# medusa-ai-power.net
KiCad netlist of a schematic drawn in Altium Designer
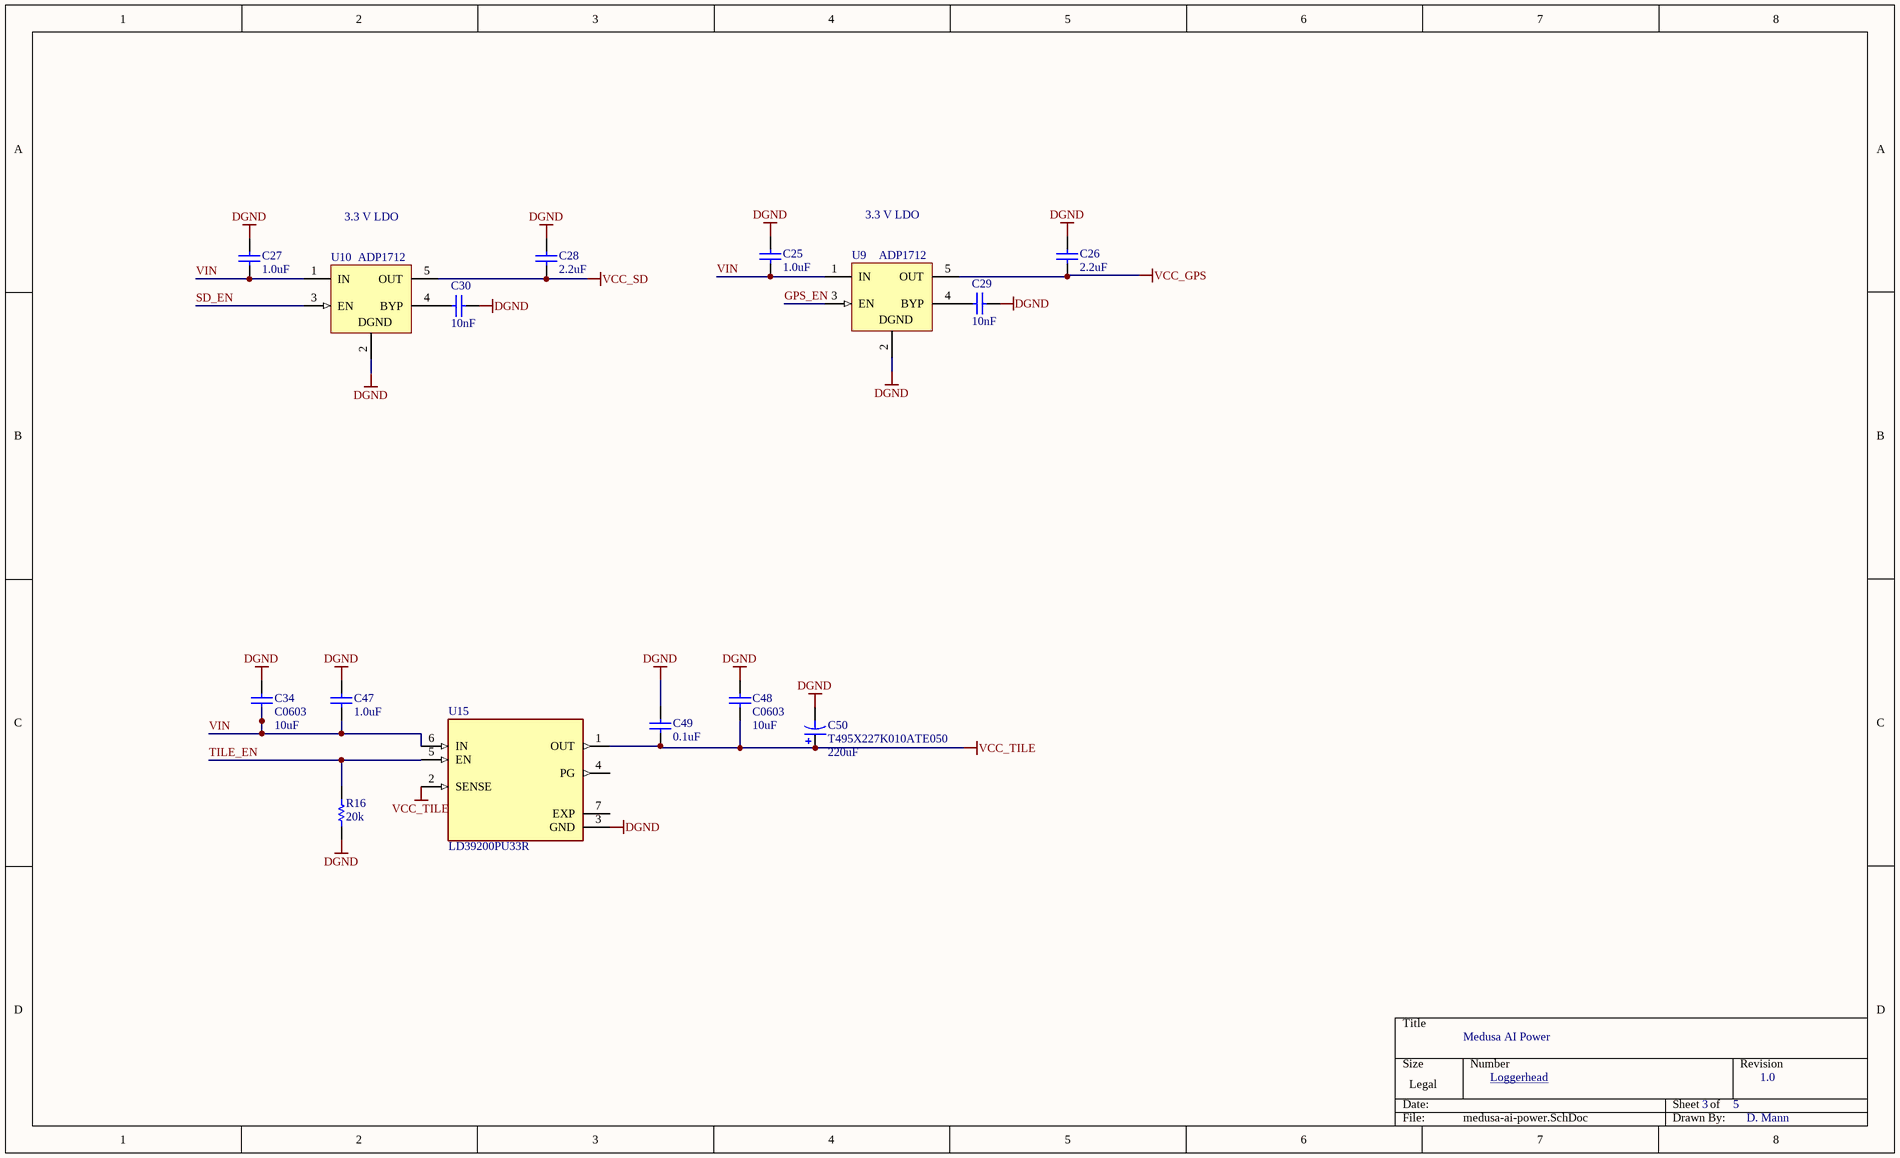
[diagram p0: medusa-ai-power.SchDoc]

(export (version "E")
  (design (tool "Eeschema 10.0.6"))
  (components
    (comp (ref "C25")
      (value "1.0uF")
      (footprint "0402")
      (description "Ceramic Chip Capacitor - Standard")
      (fields (field (name "PUBLISHER") "Altium Limited"))
      (libsource (lib "KEMET Chip Capacitor") (part "C0402"))
    )
    (comp (ref "C26")
      (value "2.2uF")
      (footprint "0402")
      (description "Ceramic Chip Capacitor - Standard")
      (fields (field (name "PUBLISHER") "Altium Limited"))
      (libsource (lib "KEMET Chip Capacitor") (part "C0402"))
    )
    (comp (ref "C27")
      (value "1.0uF")
      (footprint "0402")
      (description "Ceramic Chip Capacitor - Standard")
      (fields (field (name "PUBLISHER") "Altium Limited"))
      (libsource (lib "KEMET Chip Capacitor") (part "C0402"))
    )
    (comp (ref "C28")
      (value "2.2uF")
      (footprint "0402")
      (description "Ceramic Chip Capacitor - Standard")
      (fields (field (name "PUBLISHER") "Altium Limited"))
      (libsource (lib "KEMET Chip Capacitor") (part "C0402"))
    )
    (comp (ref "C29")
      (value "10nF")
      (footprint "0402")
      (description "Ceramic Chip Capacitor - Standard")
      (fields (field (name "PUBLISHER") "Altium Limited"))
      (libsource (lib "KEMET Chip Capacitor") (part "C0402"))
    )
    (comp (ref "C30")
      (value "10nF")
      (footprint "0402")
      (description "Ceramic Chip Capacitor - Standard")
      (fields (field (name "PUBLISHER") "Altium Limited"))
      (libsource (lib "KEMET Chip Capacitor") (part "C0402"))
    )
    (comp (ref "C34")
      (value "C0603")
      (footprint "0603")
      (description "Ceramic Chip Capacitor - Standard")
      (fields (field (name "ALTIUM_VALUE") "10uF") (field (name "PUBLISHER") "Altium Limited"))
      (libsource (lib "KEMET Chip Capacitor") (part "C0603"))
    )
    (comp (ref "C47")
      (value "1.0uF")
      (footprint "0402")
      (description "Ceramic Chip Capacitor - Standard")
      (fields (field (name "PUBLISHER") "Altium Limited"))
      (libsource (lib "KEMET Chip Capacitor") (part "C0402"))
    )
    (comp (ref "C48")
      (value "C0603")
      (footprint "0603")
      (description "Ceramic Chip Capacitor - Standard")
      (fields (field (name "ALTIUM_VALUE") "10uF") (field (name "PUBLISHER") "Altium Limited"))
      (libsource (lib "KEMET Chip Capacitor") (part "C0603"))
    )
    (comp (ref "C49")
      (value "0.1uF")
      (footprint "0402")
      (description "Ceramic Chip Capacitor - Standard")
      (fields (field (name "PUBLISHER") "Altium Limited"))
      (libsource (lib "KEMET Chip Capacitor") (part "C0402"))
    )
    (comp (ref "C50")
      (value "T495X227K010ATE050")
      (footprint "X")
      (description "Solid Tantalum Chip Capacitor, Standard T495 Series - Low ESR, Surge Robust")
      (fields (field (name "ALTIUM_VALUE") "220uF") (field (name "PUBLISHER") "Altium Limited"))
      (libsource (lib "KEMET Chip Capacitor") (part "T495X"))
    )
    (comp (ref "R16")
      (value "20k")
      (footprint "3-0603")
      (fields (field (name "PUBLISHER") "Altium Limited"))
      (libsource (lib "Panasonic Resistor") (part "ERJ3RK"))
    )
    (comp (ref "U9")
      (value "ADP1712")
      (footprint "MF05A_N")
      (description "Micropower, 150mA Low-Noise Ultra Low-Dropout CMOS Voltage Regulator")
      (fields
        (field (name "PARTNUMBER") "LP3985IM5-3.3")
        (field (name "MANUFACTURER") "National Semiconductor")
        (field (name "PUBLISHER") "Altium Limited")
      )
      (libsource (lib "NSC LDO") (part "LP3985IM5-3.3"))
    )
    (comp (ref "U10")
      (value "ADP1712")
      (footprint "MF05A_N")
      (description "Micropower, 150mA Low-Noise Ultra Low-Dropout CMOS Voltage Regulator")
      (fields
        (field (name "PARTNUMBER") "LP3985IM5-3.3")
        (field (name "MANUFACTURER") "National Semiconductor")
        (field (name "PUBLISHER") "Altium Limited")
      )
      (libsource (lib "NSC LDO") (part "LP3985IM5-3.3"))
    )
    (comp (ref "U15")
      (value "LD39200PU33R")
      (footprint "SON95P300X300X100-7N")
      (description "Linear Voltage Regulator IC 1 Output 2A 6-DFN _3x3_")
      (fields (field (name "MF") "STMicroelectronics"))
      (libsource (lib "LD39200PU33R") (part "LD39200PU33R"))
    )
  )
  (nets
    (net (code "1") (name "/GPS_EN") (class "Default")
      (node (ref "U9") (pin "3") (pinfunction "EN_3") (pintype "input"))
    )
    (net (code "2") (name "/SD_EN") (class "Default")
      (node (ref "U10") (pin "3") (pinfunction "EN_3") (pintype "input"))
    )
    (net (code "3") (name "/TILE_EN") (class "Default")
      (node (ref "R16") (pin "1") (pinfunction "1_1") (pintype "passive"))
      (node (ref "U15") (pin "5") (pinfunction "EN_5") (pintype "input"))
    )
    (net (code "4") (name "/VIN") (class "Default")
      (node (ref "C25") (pin "1") (pinfunction "1_1") (pintype "passive"))
      (node (ref "C27") (pin "1") (pinfunction "1_1") (pintype "passive"))
      (node (ref "C34") (pin "2") (pinfunction "2_2") (pintype "passive"))
      (node (ref "C47") (pin "1") (pinfunction "1_1") (pintype "passive"))
      (node (ref "U10") (pin "1") (pinfunction "IN_1") (pintype "power_in"))
      (node (ref "U15") (pin "6") (pinfunction "IN_6") (pintype "input"))
      (node (ref "U9") (pin "1") (pinfunction "IN_1") (pintype "power_in"))
    )
    (net (code "5") (name "DGND") (class "Default")
      (node (ref "C25") (pin "2") (pinfunction "2_2") (pintype "passive"))
      (node (ref "C26") (pin "2") (pinfunction "2_2") (pintype "passive"))
      (node (ref "C27") (pin "2") (pinfunction "2_2") (pintype "passive"))
      (node (ref "C28") (pin "2") (pinfunction "2_2") (pintype "passive"))
      (node (ref "C29") (pin "1") (pinfunction "1_1") (pintype "passive"))
      (node (ref "C30") (pin "1") (pinfunction "1_1") (pintype "passive"))
      (node (ref "C34") (pin "1") (pinfunction "1_1") (pintype "passive"))
      (node (ref "C47") (pin "2") (pinfunction "2_2") (pintype "passive"))
      (node (ref "C48") (pin "1") (pinfunction "1_1") (pintype "passive"))
      (node (ref "C49") (pin "2") (pinfunction "2_2") (pintype "passive"))
      (node (ref "C50") (pin "2") (pinfunction "2_2") (pintype "passive"))
      (node (ref "R16") (pin "2") (pinfunction "2_2") (pintype "passive"))
      (node (ref "U10") (pin "2") (pinfunction "GND_2") (pintype "power_in"))
      (node (ref "U15") (pin "3") (pinfunction "GND_3") (pintype "power_in"))
      (node (ref "U9") (pin "2") (pinfunction "GND_2") (pintype "power_in"))
    )
    (net (code "6") (name "Net-(U9-BYP)") (class "Default")
      (node (ref "C29") (pin "2") (pinfunction "2_2") (pintype "passive"))
      (node (ref "U9") (pin "4") (pinfunction "BYP_4") (pintype "passive"))
    )
    (net (code "7") (name "Net-(U10-BYP)") (class "Default")
      (node (ref "C30") (pin "2") (pinfunction "2_2") (pintype "passive"))
      (node (ref "U10") (pin "4") (pinfunction "BYP_4") (pintype "passive"))
    )
    (net (code "8") (name "VCC_GPS") (class "Default")
      (node (ref "C26") (pin "1") (pinfunction "1_1") (pintype "passive"))
      (node (ref "U9") (pin "5") (pinfunction "OUT_5") (pintype "power_in"))
    )
    (net (code "9") (name "VCC_SD") (class "Default")
      (node (ref "C28") (pin "1") (pinfunction "1_1") (pintype "passive"))
      (node (ref "U10") (pin "5") (pinfunction "OUT_5") (pintype "power_in"))
    )
    (net (code "10") (name "VCC_TILE") (class "Default")
      (node (ref "C48") (pin "2") (pinfunction "2_2") (pintype "passive"))
      (node (ref "C49") (pin "1") (pinfunction "1_1") (pintype "passive"))
      (node (ref "C50") (pin "1") (pinfunction "1_1") (pintype "passive"))
      (node (ref "U15") (pin "1") (pinfunction "OUT_1") (pintype "output"))
      (node (ref "U15") (pin "2") (pinfunction "SENSE_2") (pintype "input"))
    )
    (net (code "11") (name "unconnected-(U15-EXP-Pad7)") (class "Default")
      (node (ref "U15") (pin "7") (pinfunction "EXP_7") (pintype "power_in"))
    )
    (net (code "12") (name "unconnected-(U15-PG-Pad4)") (class "Default")
      (node (ref "U15") (pin "4") (pinfunction "PG_4") (pintype "output"))
    )
  )
)
